# RTC.net
KiCad netlist of a schematic drawn in Altium Designer
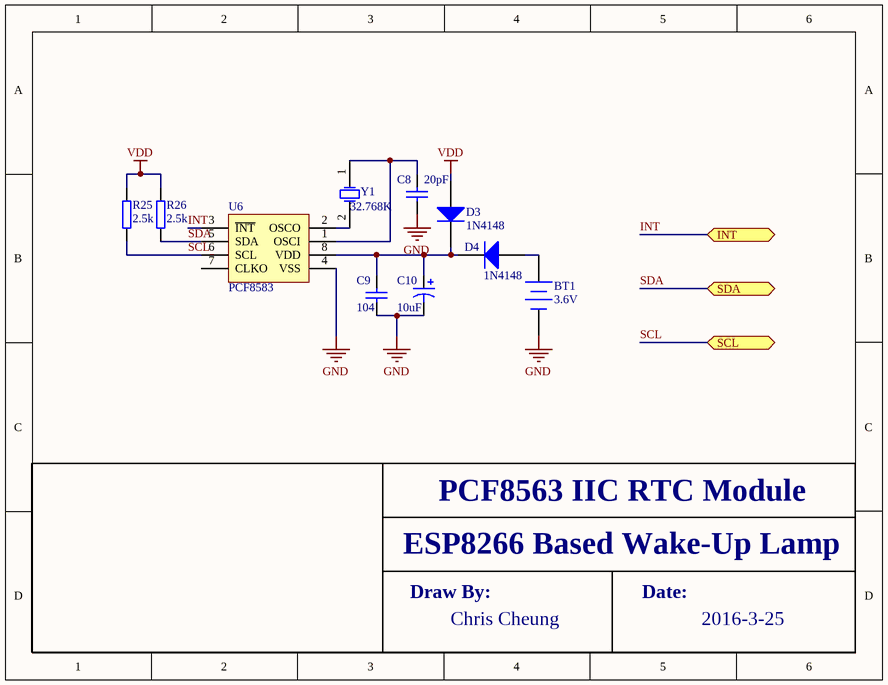
[diagram p0: RTC.SchDoc]

(export (version "E")
  (design (tool "Eeschema 10.0.6"))
  (components
    (comp (ref "BT1")
      (value "3.6V")
      (footprint "BAT-2")
      (description "Multicell Battery")
      (fields (field (name "PUBLISHER") "Altium Limited"))
      (libsource (lib "Miscellaneous Devices") (part "Battery"))
    )
    (comp (ref "C8")
      (value "20pF")
      (footprint "RAD-0.3")
      (description "Capacitor")
      (fields (field (name "Comment") "Cap") (field (name "PUBLISHER") "Altium Limited"))
      (libsource (lib "Miscellaneous Devices") (part "Cap"))
    )
    (comp (ref "C9")
      (value "104")
      (footprint "RAD-0.3")
      (description "Capacitor")
      (fields (field (name "Comment") "Cap") (field (name "PUBLISHER") "Altium Limited"))
      (libsource (lib "Miscellaneous Devices") (part "Cap"))
    )
    (comp (ref "C10")
      (value "10uF")
      (footprint "C0805")
      (description "Polarized Capacitor (Surface Mount)")
      (fields (field (name "Comment") "Cap Pol3") (field (name "PUBLISHER") "Altium Limited"))
      (libsource (lib "Miscellaneous Devices") (part "Cap Pol3"))
    )
    (comp (ref "D3")
      (value "1N4148")
      (footprint "DO-41")
      (description "1 Amp General Purpose Rectifier")
      (fields (field (name "PUBLISHER") "Altium Limited"))
      (libsource (lib "Miscellaneous Devices") (part "Diode 1N4001"))
    )
    (comp (ref "D4")
      (value "1N4148")
      (footprint "DO-41")
      (description "1 Amp General Purpose Rectifier")
      (fields (field (name "PUBLISHER") "Altium Limited"))
      (libsource (lib "Miscellaneous Devices") (part "Diode 1N4001"))
    )
    (comp (ref "R25")
      (value "2.5k")
      (footprint "SMT_R_0402")
      (description "Surface mount resistor 0402")
      (libsource (lib "Vowstar_Basic_Device") (part "SMT_R_0402"))
    )
    (comp (ref "R26")
      (value "2.5k")
      (footprint "SMT_R_0402")
      (description "Surface mount resistor 0402")
      (libsource (lib "Vowstar_Basic_Device") (part "SMT_R_0402"))
    )
    (comp (ref "U6")
      (value "PCF8583")
      (fields (field (name "Comment") "Real Time"))
      (libsource (lib "Schlib1") (part "PCF8583"))
    )
    (comp (ref "Y1")
      (value "32.768K")
      (footprint "R38")
      (description "Crystal Oscillator")
      (fields (field (name "Comment") "SMD") (field (name "PUBLISHER") "Altium Limited"))
      (libsource (lib "Miscellaneous Devices") (part "XTAL"))
    )
  )
  (nets
    (net (code "1") (name "/INT") (class "Default")
      (node (ref "U6") (pin "3") (pinfunction "~{INT}_3") (pintype "passive"))
    )
    (net (code "2") (name "/SCL") (class "Default")
      (node (ref "R25") (pin "1") (pinfunction "1_1") (pintype "passive"))
      (node (ref "U6") (pin "6") (pinfunction "SCL_6") (pintype "passive"))
    )
    (net (code "3") (name "/SDA") (class "Default")
      (node (ref "R26") (pin "1") (pinfunction "1_1") (pintype "passive"))
      (node (ref "U6") (pin "5") (pinfunction "SDA_5") (pintype "passive"))
    )
    (net (code "4") (name "GND") (class "Default")
      (node (ref "BT1") (pin "2") (pinfunction "-_2") (pintype "passive"))
      (node (ref "C10") (pin "2") (pinfunction "2_2") (pintype "passive"))
      (node (ref "C8") (pin "1") (pinfunction "1_1") (pintype "passive"))
      (node (ref "C9") (pin "1") (pinfunction "1_1") (pintype "passive"))
      (node (ref "U6") (pin "4") (pinfunction "VSS_4") (pintype "passive"))
    )
    (net (code "5") (name "Net-(BT1-+)") (class "Default")
      (node (ref "BT1") (pin "1") (pinfunction "+_1") (pintype "passive"))
      (node (ref "D4") (pin "1") (pinfunction "A_1") (pintype "passive"))
    )
    (net (code "6") (name "Net-(D3-K)") (class "Default")
      (node (ref "C10") (pin "1") (pinfunction "1_1") (pintype "passive"))
      (node (ref "C9") (pin "2") (pinfunction "2_2") (pintype "passive"))
      (node (ref "D3") (pin "2") (pinfunction "K_2") (pintype "passive"))
      (node (ref "D4") (pin "2") (pinfunction "K_2") (pintype "passive"))
      (node (ref "U6") (pin "8") (pinfunction "VDD_8") (pintype "passive"))
    )
    (net (code "7") (name "Net-(U6-OSCI)") (class "Default")
      (node (ref "C8") (pin "2") (pinfunction "2_2") (pintype "passive"))
      (node (ref "U6") (pin "1") (pinfunction "OSCI_1") (pintype "passive"))
      (node (ref "Y1") (pin "1") (pinfunction "OSC1_1") (pintype "passive"))
    )
    (net (code "8") (name "Net-(U6-OSCO)") (class "Default")
      (node (ref "U6") (pin "2") (pinfunction "OSCO_2") (pintype "passive"))
      (node (ref "Y1") (pin "2") (pinfunction "OSC2_2") (pintype "passive"))
    )
    (net (code "9") (name "VDD") (class "Default")
      (node (ref "D3") (pin "1") (pinfunction "A_1") (pintype "passive"))
      (node (ref "R25") (pin "2") (pinfunction "2_2") (pintype "passive"))
      (node (ref "R26") (pin "2") (pinfunction "2_2") (pintype "passive"))
    )
    (net (code "10") (name "unconnected-(U6-CLKO-Pad7)") (class "Default")
      (node (ref "U6") (pin "7") (pinfunction "CLKO_7") (pintype "passive"))
    )
  )
)
